# voice_sample.net
KiCad netlist of a schematic drawn in Altium Designer
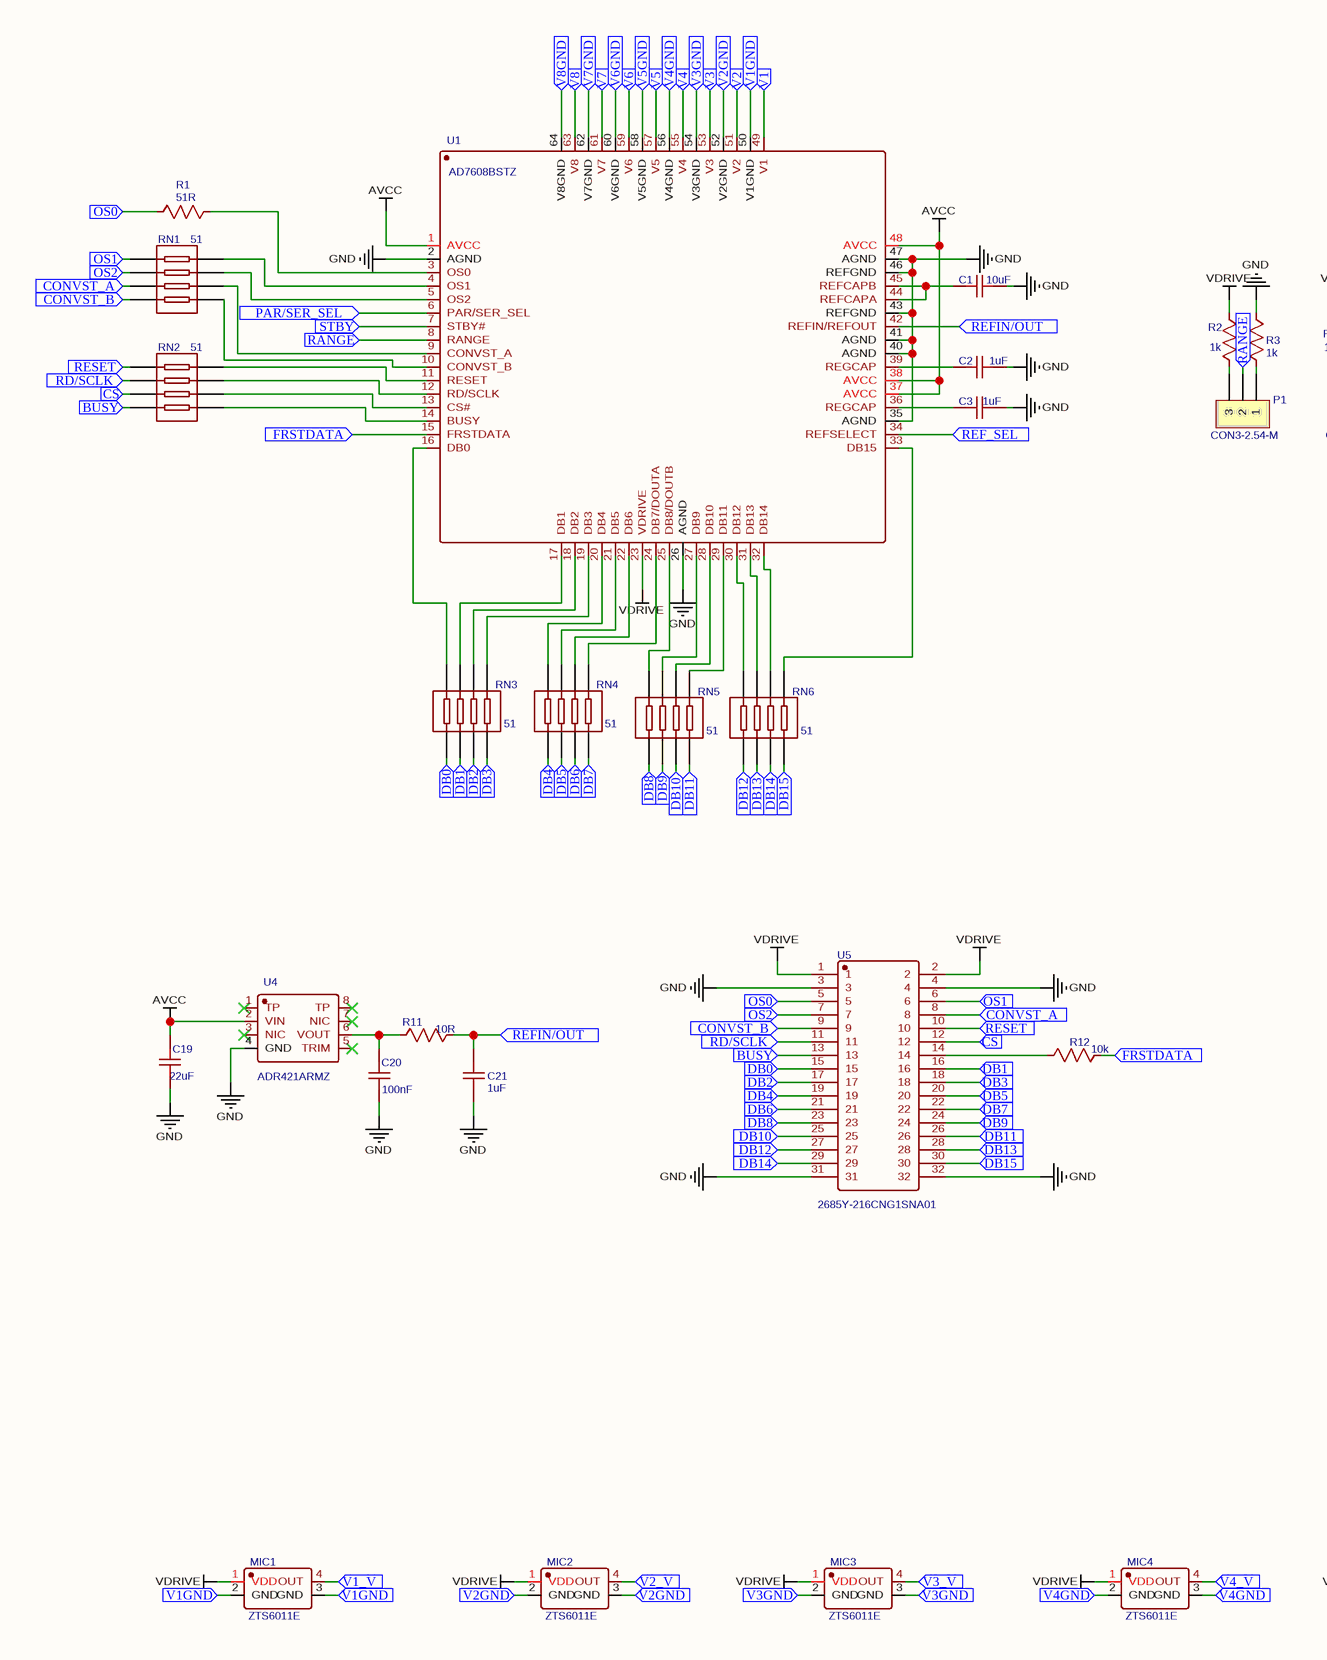
[diagram p0: voice_sample.schdoc, left]
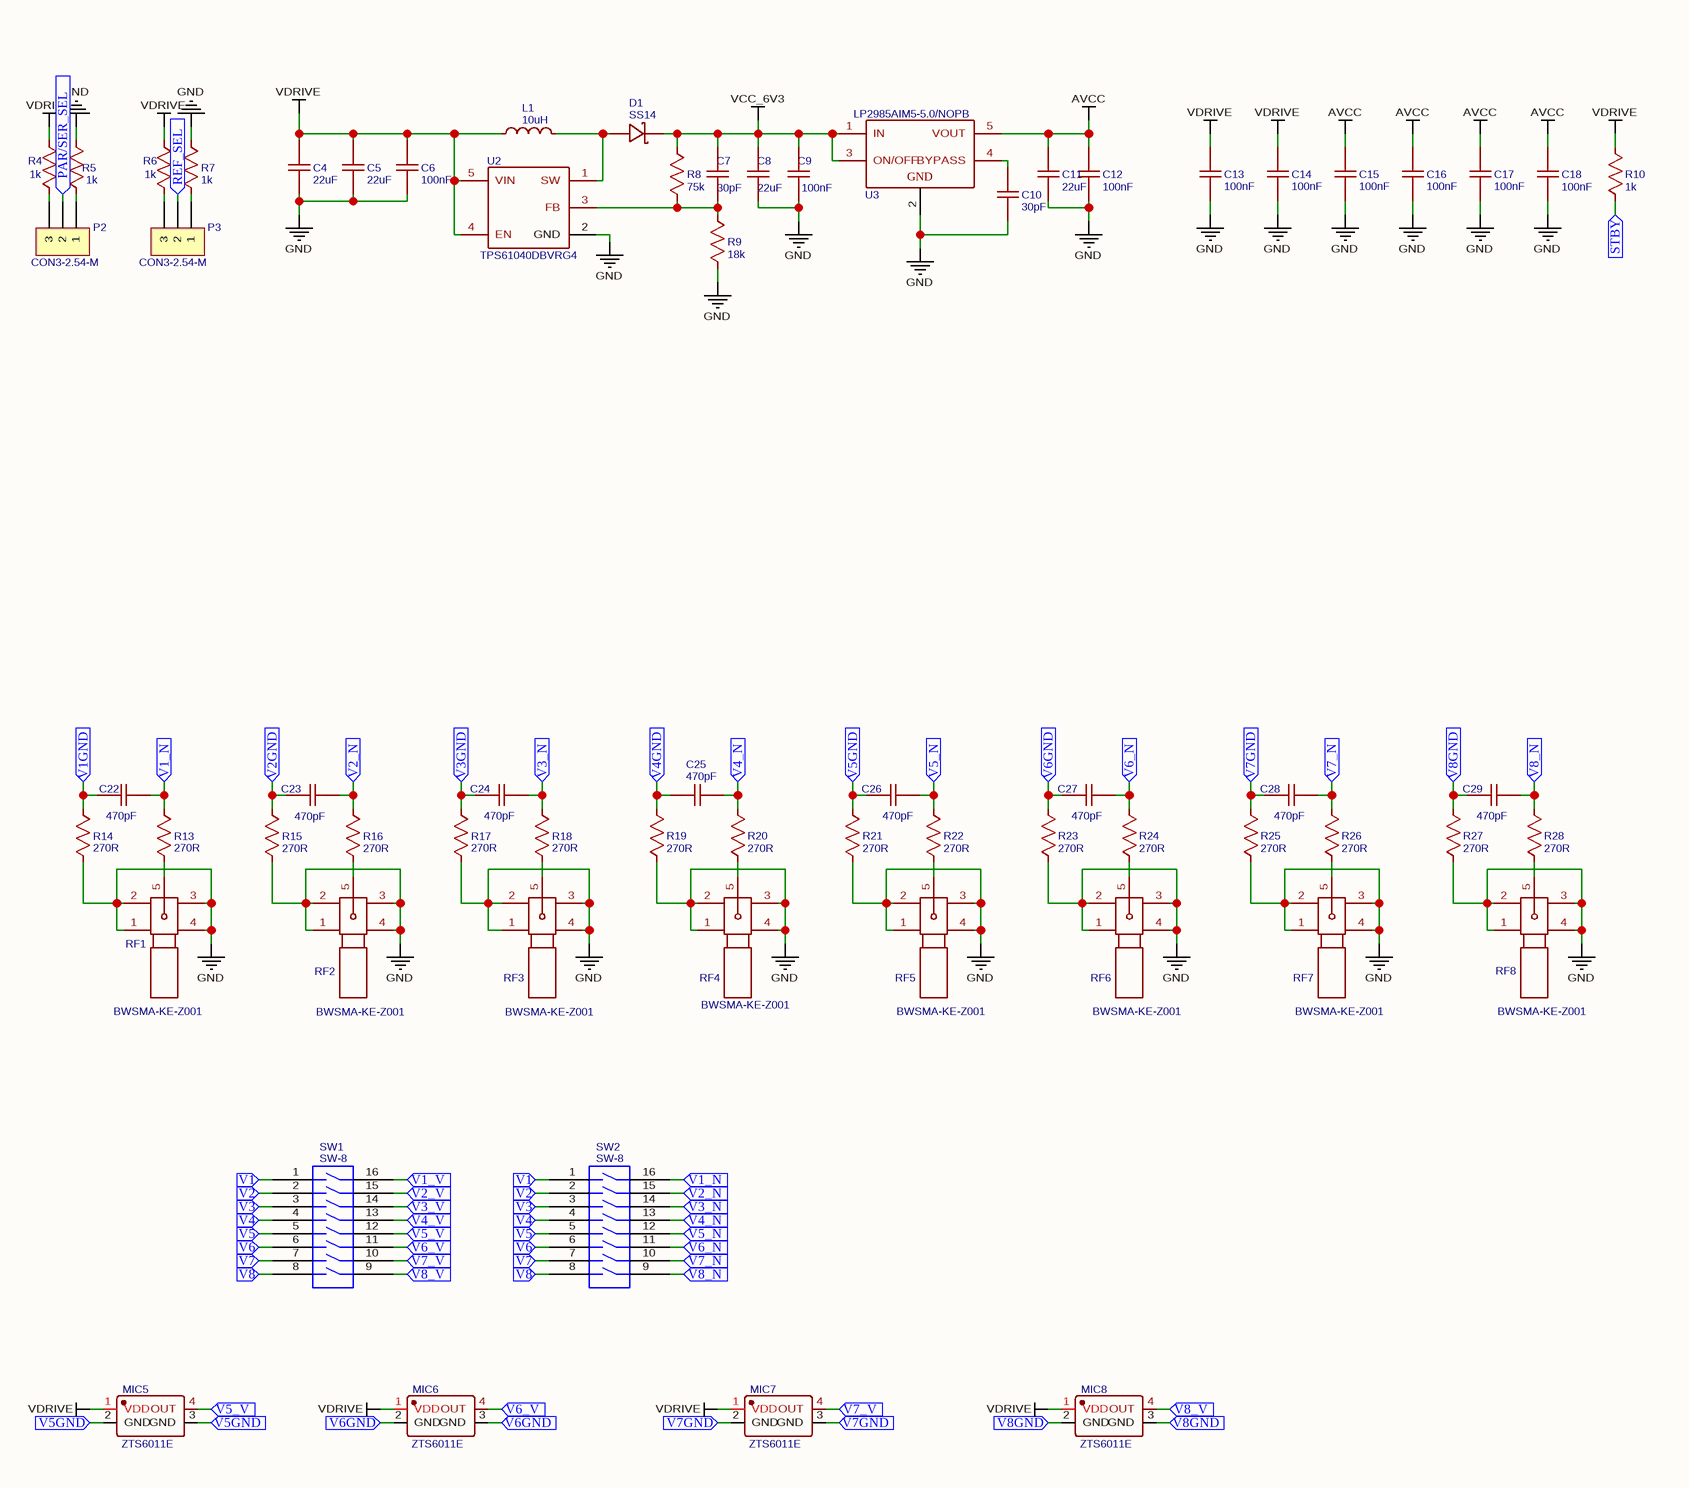
[diagram p1: voice_sample.schdoc, right]

(export (version "E")
  (design (tool "Eeschema 10.0.6"))
  (components
    (comp (ref "C1") (value "10uF") (libsource (lib "altium-import") (part "root_0_10uF_")))
    (comp (ref "C2") (value "1uF") (libsource (lib "altium-import") (part "root_0_1uF_")))
    (comp (ref "C3") (value "1uF") (libsource (lib "altium-import") (part "root_0_1uF_")))
    (comp (ref "C4") (value "22uF") (libsource (lib "altium-import") (part "root_1_22uF_")))
    (comp (ref "C5") (value "22uF") (libsource (lib "altium-import") (part "root_1_22uF_")))
    (comp (ref "C6") (value "100nF") (libsource (lib "altium-import") (part "root_1_100nF_")))
    (comp (ref "C7") (value "30pF") (libsource (lib "altium-import") (part "root_1_30pF_")))
    (comp (ref "C8") (value "22uF") (libsource (lib "altium-import") (part "root_1_22uF_")))
    (comp (ref "C9") (value "100nF") (libsource (lib "altium-import") (part "root_1_100nF_")))
    (comp (ref "C10") (value "30pF") (libsource (lib "altium-import") (part "root_1_30pF_")))
    (comp (ref "C11") (value "22uF") (libsource (lib "altium-import") (part "root_1_22uF_")))
    (comp (ref "C12") (value "100nF") (libsource (lib "altium-import") (part "root_1_100nF_")))
    (comp (ref "C13") (value "100nF") (libsource (lib "altium-import") (part "root_1_100nF_")))
    (comp (ref "C14") (value "100nF") (libsource (lib "altium-import") (part "root_1_100nF_")))
    (comp (ref "C15") (value "100nF") (libsource (lib "altium-import") (part "root_1_100nF_")))
    (comp (ref "C16") (value "100nF") (libsource (lib "altium-import") (part "root_1_100nF_")))
    (comp (ref "C17") (value "100nF") (libsource (lib "altium-import") (part "root_1_100nF_")))
    (comp (ref "C18") (value "100nF") (libsource (lib "altium-import") (part "root_1_100nF_")))
    (comp (ref "C19") (value "22uF") (libsource (lib "altium-import") (part "root_1_22uF_")))
    (comp (ref "C20") (value "100nF") (libsource (lib "altium-import") (part "root_1_100nF_")))
    (comp (ref "C21") (value "1uF") (libsource (lib "altium-import") (part "root_1_1uF_")))
    (comp (ref "C22") (value "470pF") (libsource (lib "altium-import") (part "root_0_470pF_")))
    (comp (ref "C23") (value "470pF") (libsource (lib "altium-import") (part "root_0_470pF_")))
    (comp (ref "C24") (value "470pF") (libsource (lib "altium-import") (part "root_0_470pF_")))
    (comp (ref "C25") (value "470pF") (libsource (lib "altium-import") (part "root_2_470pF_")))
    (comp (ref "C26") (value "470pF") (libsource (lib "altium-import") (part "root_0_470pF_")))
    (comp (ref "C27") (value "470pF") (libsource (lib "altium-import") (part "root_0_470pF_")))
    (comp (ref "C28") (value "470pF") (libsource (lib "altium-import") (part "root_0_470pF_")))
    (comp (ref "C29") (value "470pF") (libsource (lib "altium-import") (part "root_0_470pF_")))
    (comp (ref "D1")
      (value "SS14")
      (fields (field (name "BOM_SUPPLIER PART") "C2480"))
      (libsource (lib "altium-import") (part "root_2_SS14_"))
    )
    (comp (ref "L1") (value "10uH") (libsource (lib "altium-import") (part "root_0_10uH_")))
    (comp (ref "MIC1")
      (value "ZTS6011E")
      (fields (field (name "BOM_SUPPLIER PART") "C481291"))
      (libsource (lib "altium-import") (part "root_0_ZTS6011E_"))
    )
    (comp (ref "MIC2")
      (value "ZTS6011E")
      (fields (field (name "BOM_SUPPLIER PART") "C481291"))
      (libsource (lib "altium-import") (part "root_0_ZTS6011E_"))
    )
    (comp (ref "MIC3")
      (value "ZTS6011E")
      (fields (field (name "BOM_SUPPLIER PART") "C481291"))
      (libsource (lib "altium-import") (part "root_0_ZTS6011E_"))
    )
    (comp (ref "MIC4")
      (value "ZTS6011E")
      (fields (field (name "BOM_SUPPLIER PART") "C481291"))
      (libsource (lib "altium-import") (part "root_0_ZTS6011E_"))
    )
    (comp (ref "MIC5")
      (value "ZTS6011E")
      (fields (field (name "BOM_SUPPLIER PART") "C481291"))
      (libsource (lib "altium-import") (part "root_0_ZTS6011E_"))
    )
    (comp (ref "MIC6")
      (value "ZTS6011E")
      (fields (field (name "BOM_SUPPLIER PART") "C481291"))
      (libsource (lib "altium-import") (part "root_0_ZTS6011E_"))
    )
    (comp (ref "MIC7")
      (value "ZTS6011E")
      (fields (field (name "BOM_SUPPLIER PART") "C481291"))
      (libsource (lib "altium-import") (part "root_0_ZTS6011E_"))
    )
    (comp (ref "MIC8")
      (value "ZTS6011E")
      (fields (field (name "BOM_SUPPLIER PART") "C481291"))
      (libsource (lib "altium-import") (part "root_0_ZTS6011E_"))
    )
    (comp (ref "P1") (value "CON3-2.54-M") (libsource (lib "altium-import") (part "root_3_CON3-2.54-M_")))
    (comp (ref "P2") (value "CON3-2.54-M") (libsource (lib "altium-import") (part "root_3_CON3-2.54-M_")))
    (comp (ref "P3") (value "CON3-2.54-M") (libsource (lib "altium-import") (part "root_3_CON3-2.54-M_")))
    (comp (ref "R1") (value "51R") (libsource (lib "altium-import") (part "root_0_51R_")))
    (comp (ref "R2") (value "1k") (libsource (lib "altium-import") (part "root_1_1k_")))
    (comp (ref "R3") (value "1k") (libsource (lib "altium-import") (part "root_1_1k_")))
    (comp (ref "R4") (value "1k") (libsource (lib "altium-import") (part "root_1_1k_")))
    (comp (ref "R5") (value "1k") (libsource (lib "altium-import") (part "root_1_1k_")))
    (comp (ref "R6") (value "1k") (libsource (lib "altium-import") (part "root_1_1k_")))
    (comp (ref "R7") (value "1k") (libsource (lib "altium-import") (part "root_1_1k_")))
    (comp (ref "R8") (value "75k") (libsource (lib "altium-import") (part "root_1_75k_")))
    (comp (ref "R9") (value "18k") (libsource (lib "altium-import") (part "root_1_18k_")))
    (comp (ref "R10") (value "1k") (libsource (lib "altium-import") (part "root_1_1k_")))
    (comp (ref "R11") (value "10R") (libsource (lib "altium-import") (part "root_0_10R_")))
    (comp (ref "R12") (value "10k") (libsource (lib "altium-import") (part "root_0_10k_")))
    (comp (ref "R13") (value "270R") (libsource (lib "altium-import") (part "root_1_270R_")))
    (comp (ref "R14") (value "270R") (libsource (lib "altium-import") (part "root_1_270R_")))
    (comp (ref "R15") (value "270R") (libsource (lib "altium-import") (part "root_1_270R_")))
    (comp (ref "R16") (value "270R") (libsource (lib "altium-import") (part "root_1_270R_")))
    (comp (ref "R17") (value "270R") (libsource (lib "altium-import") (part "root_1_270R_")))
    (comp (ref "R18") (value "270R") (libsource (lib "altium-import") (part "root_1_270R_")))
    (comp (ref "R19") (value "270R") (libsource (lib "altium-import") (part "root_1_270R_")))
    (comp (ref "R20") (value "270R") (libsource (lib "altium-import") (part "root_1_270R_")))
    (comp (ref "R21") (value "270R") (libsource (lib "altium-import") (part "root_1_270R_")))
    (comp (ref "R22") (value "270R") (libsource (lib "altium-import") (part "root_1_270R_")))
    (comp (ref "R23") (value "270R") (libsource (lib "altium-import") (part "root_1_270R_")))
    (comp (ref "R24") (value "270R") (libsource (lib "altium-import") (part "root_1_270R_")))
    (comp (ref "R25") (value "270R") (libsource (lib "altium-import") (part "root_1_270R_")))
    (comp (ref "R26") (value "270R") (libsource (lib "altium-import") (part "root_1_270R_")))
    (comp (ref "R27") (value "270R") (libsource (lib "altium-import") (part "root_1_270R_")))
    (comp (ref "R28") (value "270R") (libsource (lib "altium-import") (part "root_1_270R_")))
    (comp (ref "RF1")
      (value "BWSMA-KE-Z001")
      (fields (field (name "BOM_SUPPLIER PART") "C496549"))
      (libsource (lib "altium-import") (part "root_1_BWSMA-KE-Z001_"))
    )
    (comp (ref "RF2")
      (value "BWSMA-KE-Z001")
      (fields (field (name "BOM_SUPPLIER PART") "C496549"))
      (libsource (lib "altium-import") (part "root_1_BWSMA-KE-Z001_"))
    )
    (comp (ref "RF3")
      (value "BWSMA-KE-Z001")
      (fields (field (name "BOM_SUPPLIER PART") "C496549"))
      (libsource (lib "altium-import") (part "root_1_BWSMA-KE-Z001_"))
    )
    (comp (ref "RF4")
      (value "BWSMA-KE-Z001")
      (fields (field (name "BOM_SUPPLIER PART") "C496549"))
      (libsource (lib "altium-import") (part "root_1_BWSMA-KE-Z001_"))
    )
    (comp (ref "RF5")
      (value "BWSMA-KE-Z001")
      (fields (field (name "BOM_SUPPLIER PART") "C496549"))
      (libsource (lib "altium-import") (part "root_1_BWSMA-KE-Z001_"))
    )
    (comp (ref "RF6")
      (value "BWSMA-KE-Z001")
      (fields (field (name "BOM_SUPPLIER PART") "C496549"))
      (libsource (lib "altium-import") (part "root_1_BWSMA-KE-Z001_"))
    )
    (comp (ref "RF7")
      (value "BWSMA-KE-Z001")
      (fields (field (name "BOM_SUPPLIER PART") "C496549"))
      (libsource (lib "altium-import") (part "root_1_BWSMA-KE-Z001_"))
    )
    (comp (ref "RF8")
      (value "BWSMA-KE-Z001")
      (fields (field (name "BOM_SUPPLIER PART") "C496549"))
      (libsource (lib "altium-import") (part "root_1_BWSMA-KE-Z001_"))
    )
    (comp (ref "RN1")
      (value "51")
      (fields
        (field (name "BOM_MANUFACTURER PART") "RTA02-4D510JTH")
        (field (name "BOM_SUPPLIER PART") "C102639")
      )
      (libsource (lib "altium-import") (part "root_1_51_"))
    )
    (comp (ref "RN2")
      (value "51")
      (fields
        (field (name "BOM_MANUFACTURER PART") "RTA02-4D510JTH")
        (field (name "BOM_SUPPLIER PART") "C102639")
      )
      (libsource (lib "altium-import") (part "root_1_51_"))
    )
    (comp (ref "RN3")
      (value "51")
      (fields
        (field (name "BOM_MANUFACTURER PART") "RTA02-4D510JTH")
        (field (name "BOM_SUPPLIER PART") "C102639")
      )
      (libsource (lib "altium-import") (part "root_0_51_"))
    )
    (comp (ref "RN4")
      (value "51")
      (fields
        (field (name "BOM_MANUFACTURER PART") "RTA02-4D510JTH")
        (field (name "BOM_SUPPLIER PART") "C102639")
      )
      (libsource (lib "altium-import") (part "root_0_51_"))
    )
    (comp (ref "RN5")
      (value "51")
      (fields
        (field (name "BOM_MANUFACTURER PART") "RTA02-4D510JTH")
        (field (name "BOM_SUPPLIER PART") "C102639")
      )
      (libsource (lib "altium-import") (part "root_0_51_"))
    )
    (comp (ref "RN6")
      (value "51")
      (fields
        (field (name "BOM_MANUFACTURER PART") "RTA02-4D510JTH")
        (field (name "BOM_SUPPLIER PART") "C102639")
      )
      (libsource (lib "altium-import") (part "root_0_51_"))
    )
    (comp (ref "SW1") (value "SW-8") (libsource (lib "altium-import") (part "root_0_SW-8_")))
    (comp (ref "SW2") (value "SW-8") (libsource (lib "altium-import") (part "root_0_SW-8_")))
    (comp (ref "U1")
      (value "AD7608BSTZ")
      (fields (field (name "BOM_SUPPLIER PART") "C128619"))
      (libsource (lib "altium-import") (part "root_0_AD7608BSTZ_"))
    )
    (comp (ref "U2")
      (value "TPS61040DBVRG4")
      (libsource (lib "altium-import") (part "root_0_TPS61040DBVRG4_"))
    )
    (comp (ref "U3")
      (value "LP2985AIM5-5.0/NOPB")
      (fields (field (name "BOM_SUPPLIER PART") "C130188"))
      (libsource (lib "altium-import") (part "root_0_LP2985AIM5-5.0/NOPB_"))
    )
    (comp (ref "U4")
      (value "ADR421ARMZ")
      (fields (field (name "BOM_SUPPLIER PART") "C659530"))
      (libsource (lib "altium-import") (part "root_0_ADR421ARMZ_"))
    )
    (comp (ref "U5")
      (value "2685Y-216CNG1SNA01")
      (fields (field (name "BOM_SUPPLIER PART") "C350290"))
      (libsource (lib "altium-import") (part "root_3_2685Y-216CNG1SNA01_"))
    )
  )
  (nets
    (net (code "1") (name "/BUSY") (class "Default")
      (node (ref "RN2") (pin "8") (pinfunction "8_8") (pintype "passive"))
      (node (ref "U5") (pin "13") (pinfunction "13_13") (pintype "passive"))
    )
    (net (code "2") (name "/CONVST_A") (class "Default")
      (node (ref "RN1") (pin "7") (pinfunction "7_7") (pintype "passive"))
      (node (ref "U5") (pin "8") (pinfunction "8_8") (pintype "passive"))
    )
    (net (code "3") (name "/CONVST_B") (class "Default")
      (node (ref "RN1") (pin "8") (pinfunction "8_8") (pintype "passive"))
      (node (ref "U5") (pin "9") (pinfunction "9_9") (pintype "passive"))
    )
    (net (code "4") (name "/CS") (class "Default")
      (node (ref "RN2") (pin "7") (pinfunction "7_7") (pintype "passive"))
      (node (ref "U5") (pin "12") (pinfunction "12_12") (pintype "passive"))
    )
    (net (code "5") (name "/DB0") (class "Default")
      (node (ref "RN3") (pin "1") (pinfunction "1_1") (pintype "passive"))
      (node (ref "U5") (pin "15") (pinfunction "15_15") (pintype "passive"))
    )
    (net (code "6") (name "/DB1") (class "Default")
      (node (ref "RN3") (pin "2") (pinfunction "2_2") (pintype "passive"))
      (node (ref "U5") (pin "16") (pinfunction "16_16") (pintype "passive"))
    )
    (net (code "7") (name "/DB2") (class "Default")
      (node (ref "RN3") (pin "3") (pinfunction "3_3") (pintype "passive"))
      (node (ref "U5") (pin "17") (pinfunction "17_17") (pintype "passive"))
    )
    (net (code "8") (name "/DB3") (class "Default")
      (node (ref "RN3") (pin "4") (pinfunction "4_4") (pintype "passive"))
      (node (ref "U5") (pin "18") (pinfunction "18_18") (pintype "passive"))
    )
    (net (code "9") (name "/DB4") (class "Default")
      (node (ref "RN4") (pin "1") (pinfunction "1_1") (pintype "passive"))
      (node (ref "U5") (pin "19") (pinfunction "19_19") (pintype "passive"))
    )
    (net (code "10") (name "/DB5") (class "Default")
      (node (ref "RN4") (pin "2") (pinfunction "2_2") (pintype "passive"))
      (node (ref "U5") (pin "20") (pinfunction "20_20") (pintype "passive"))
    )
    (net (code "11") (name "/DB6") (class "Default")
      (node (ref "RN4") (pin "3") (pinfunction "3_3") (pintype "passive"))
      (node (ref "U5") (pin "21") (pinfunction "21_21") (pintype "passive"))
    )
    (net (code "12") (name "/DB7") (class "Default")
      (node (ref "RN4") (pin "4") (pinfunction "4_4") (pintype "passive"))
      (node (ref "U5") (pin "22") (pinfunction "22_22") (pintype "passive"))
    )
    (net (code "13") (name "/DB8") (class "Default")
      (node (ref "RN5") (pin "1") (pinfunction "1_1") (pintype "passive"))
      (node (ref "U5") (pin "23") (pinfunction "23_23") (pintype "passive"))
    )
    (net (code "14") (name "/DB9") (class "Default")
      (node (ref "RN5") (pin "2") (pinfunction "2_2") (pintype "passive"))
      (node (ref "U5") (pin "24") (pinfunction "24_24") (pintype "passive"))
    )
    (net (code "15") (name "/DB10") (class "Default")
      (node (ref "RN5") (pin "3") (pinfunction "3_3") (pintype "passive"))
      (node (ref "U5") (pin "25") (pinfunction "25_25") (pintype "passive"))
    )
    (net (code "16") (name "/DB11") (class "Default")
      (node (ref "RN5") (pin "4") (pinfunction "4_4") (pintype "passive"))
      (node (ref "U5") (pin "26") (pinfunction "26_26") (pintype "passive"))
    )
    (net (code "17") (name "/DB12") (class "Default")
      (node (ref "RN6") (pin "1") (pinfunction "1_1") (pintype "passive"))
      (node (ref "U5") (pin "27") (pinfunction "27_27") (pintype "passive"))
    )
    (net (code "18") (name "/DB13") (class "Default")
      (node (ref "RN6") (pin "2") (pinfunction "2_2") (pintype "passive"))
      (node (ref "U5") (pin "28") (pinfunction "28_28") (pintype "passive"))
    )
    (net (code "19") (name "/DB14") (class "Default")
      (node (ref "RN6") (pin "3") (pinfunction "3_3") (pintype "passive"))
      (node (ref "U5") (pin "29") (pinfunction "29_29") (pintype "passive"))
    )
    (net (code "20") (name "/DB15") (class "Default")
      (node (ref "RN6") (pin "4") (pinfunction "4_4") (pintype "passive"))
      (node (ref "U5") (pin "30") (pinfunction "30_30") (pintype "passive"))
    )
    (net (code "21") (name "/FRSTDATA") (class "Default")
      (node (ref "R12") (pin "2") (pinfunction "2_2") (pintype "passive"))
      (node (ref "U1") (pin "15") (pinfunction "FRSTDATA_15") (pintype "passive"))
    )
    (net (code "22") (name "/OS0") (class "Default")
      (node (ref "R1") (pin "1") (pinfunction "1_1") (pintype "passive"))
      (node (ref "U5") (pin "5") (pinfunction "5_5") (pintype "passive"))
    )
    (net (code "23") (name "/OS1") (class "Default")
      (node (ref "RN1") (pin "5") (pinfunction "5_5") (pintype "passive"))
      (node (ref "U5") (pin "6") (pinfunction "6_6") (pintype "passive"))
    )
    (net (code "24") (name "/OS2") (class "Default")
      (node (ref "RN1") (pin "6") (pinfunction "6_6") (pintype "passive"))
      (node (ref "U5") (pin "7") (pinfunction "7_7") (pintype "passive"))
    )
    (net (code "25") (name "/PAR{slash}SER_SEL") (class "Default")
      (node (ref "P2") (pin "2") (pinfunction "2_2") (pintype "passive"))
      (node (ref "U1") (pin "6") (pinfunction "PAR/SER_SEL_6") (pintype "passive"))
    )
    (net (code "26") (name "/RANGE") (class "Default")
      (node (ref "P1") (pin "2") (pinfunction "2_2") (pintype "passive"))
      (node (ref "U1") (pin "8") (pinfunction "RANGE_8") (pintype "passive"))
    )
    (net (code "27") (name "/RD{slash}SCLK") (class "Default")
      (node (ref "RN2") (pin "6") (pinfunction "6_6") (pintype "passive"))
      (node (ref "U5") (pin "11") (pinfunction "11_11") (pintype "passive"))
    )
    (net (code "28") (name "/REFIN{slash}OUT") (class "Default")
      (node (ref "C21") (pin "2") (pinfunction "2_2") (pintype "passive"))
      (node (ref "R11") (pin "2") (pinfunction "2_2") (pintype "passive"))
      (node (ref "U1") (pin "42") (pinfunction "REFIN/REFOUT_42") (pintype "passive"))
    )
    (net (code "29") (name "/REF_SEL") (class "Default")
      (node (ref "P3") (pin "2") (pinfunction "2_2") (pintype "passive"))
      (node (ref "U1") (pin "34") (pinfunction "REFSELECT_34") (pintype "passive"))
    )
    (net (code "30") (name "/RESET") (class "Default")
      (node (ref "RN2") (pin "5") (pinfunction "5_5") (pintype "passive"))
      (node (ref "U5") (pin "10") (pinfunction "10_10") (pintype "passive"))
    )
    (net (code "31") (name "/STBY") (class "Default")
      (node (ref "R10") (pin "1") (pinfunction "1_1") (pintype "passive"))
      (node (ref "U1") (pin "7") (pinfunction "STBY#_7") (pintype "passive"))
    )
    (net (code "32") (name "/V1") (class "Default")
      (node (ref "SW1") (pin "1") (pintype "passive"))
      (node (ref "SW2") (pin "1") (pintype "passive"))
      (node (ref "U1") (pin "49") (pinfunction "V1_49") (pintype "passive"))
    )
    (net (code "33") (name "/V1GND") (class "Default")
      (node (ref "C22") (pin "1") (pinfunction "1_1") (pintype "passive"))
      (node (ref "MIC1") (pin "2") (pinfunction "GND_2") (pintype "passive"))
      (node (ref "MIC1") (pin "3") (pinfunction "GND_3") (pintype "passive"))
      (node (ref "R14") (pin "2") (pinfunction "2_2") (pintype "passive"))
      (node (ref "U1") (pin "50") (pinfunction "V1GND_50") (pintype "passive"))
    )
    (net (code "34") (name "/V1_N") (class "Default")
      (node (ref "C22") (pin "2") (pinfunction "2_2") (pintype "passive"))
      (node (ref "R13") (pin "2") (pinfunction "2_2") (pintype "passive"))
      (node (ref "SW2") (pin "16") (pintype "passive"))
    )
    (net (code "35") (name "/V1_V") (class "Default")
      (node (ref "MIC1") (pin "4") (pinfunction "OUT_4") (pintype "passive"))
      (node (ref "SW1") (pin "16") (pintype "passive"))
    )
    (net (code "36") (name "/V2") (class "Default")
      (node (ref "SW1") (pin "2") (pintype "passive"))
      (node (ref "SW2") (pin "2") (pintype "passive"))
      (node (ref "U1") (pin "51") (pinfunction "V2_51") (pintype "passive"))
    )
    (net (code "37") (name "/V2GND") (class "Default")
      (node (ref "C23") (pin "1") (pinfunction "1_1") (pintype "passive"))
      (node (ref "MIC2") (pin "2") (pinfunction "GND_2") (pintype "passive"))
      (node (ref "MIC2") (pin "3") (pinfunction "GND_3") (pintype "passive"))
      (node (ref "R15") (pin "2") (pinfunction "2_2") (pintype "passive"))
      (node (ref "U1") (pin "52") (pinfunction "V2GND_52") (pintype "passive"))
    )
    (net (code "38") (name "/V2_N") (class "Default")
      (node (ref "C23") (pin "2") (pinfunction "2_2") (pintype "passive"))
      (node (ref "R16") (pin "2") (pinfunction "2_2") (pintype "passive"))
      (node (ref "SW2") (pin "15") (pintype "passive"))
    )
    (net (code "39") (name "/V2_V") (class "Default")
      (node (ref "MIC2") (pin "4") (pinfunction "OUT_4") (pintype "passive"))
      (node (ref "SW1") (pin "15") (pintype "passive"))
    )
    (net (code "40") (name "/V3") (class "Default")
      (node (ref "SW1") (pin "3") (pintype "passive"))
      (node (ref "SW2") (pin "3") (pintype "passive"))
      (node (ref "U1") (pin "53") (pinfunction "V3_53") (pintype "passive"))
    )
    (net (code "41") (name "/V3GND") (class "Default")
      (node (ref "C24") (pin "1") (pinfunction "1_1") (pintype "passive"))
      (node (ref "MIC3") (pin "2") (pinfunction "GND_2") (pintype "passive"))
      (node (ref "MIC3") (pin "3") (pinfunction "GND_3") (pintype "passive"))
      (node (ref "R17") (pin "2") (pinfunction "2_2") (pintype "passive"))
      (node (ref "U1") (pin "54") (pinfunction "V3GND_54") (pintype "passive"))
    )
    (net (code "42") (name "/V3_N") (class "Default")
      (node (ref "C24") (pin "2") (pinfunction "2_2") (pintype "passive"))
      (node (ref "R18") (pin "2") (pinfunction "2_2") (pintype "passive"))
      (node (ref "SW2") (pin "14") (pintype "passive"))
    )
    (net (code "43") (name "/V3_V") (class "Default")
      (node (ref "MIC3") (pin "4") (pinfunction "OUT_4") (pintype "passive"))
      (node (ref "SW1") (pin "14") (pintype "passive"))
    )
    (net (code "44") (name "/V4") (class "Default")
      (node (ref "SW1") (pin "4") (pintype "passive"))
      (node (ref "SW2") (pin "4") (pintype "passive"))
      (node (ref "U1") (pin "55") (pinfunction "V4_55") (pintype "passive"))
    )
    (net (code "45") (name "/V4GND") (class "Default")
      (node (ref "C25") (pin "2") (pinfunction "2_2") (pintype "passive"))
      (node (ref "MIC4") (pin "2") (pinfunction "GND_2") (pintype "passive"))
      (node (ref "MIC4") (pin "3") (pinfunction "GND_3") (pintype "passive"))
      (node (ref "R19") (pin "2") (pinfunction "2_2") (pintype "passive"))
      (node (ref "U1") (pin "56") (pinfunction "V4GND_56") (pintype "passive"))
    )
    (net (code "46") (name "/V4_N") (class "Default")
      (node (ref "C25") (pin "1") (pinfunction "1_1") (pintype "passive"))
      (node (ref "R20") (pin "2") (pinfunction "2_2") (pintype "passive"))
      (node (ref "SW2") (pin "13") (pintype "passive"))
    )
    (net (code "47") (name "/V4_V") (class "Default")
      (node (ref "MIC4") (pin "4") (pinfunction "OUT_4") (pintype "passive"))
      (node (ref "SW1") (pin "13") (pintype "passive"))
    )
    (net (code "48") (name "/V5") (class "Default")
      (node (ref "SW1") (pin "5") (pintype "passive"))
      (node (ref "SW2") (pin "5") (pintype "passive"))
      (node (ref "U1") (pin "57") (pinfunction "V5_57") (pintype "passive"))
    )
    (net (code "49") (name "/V5GND") (class "Default")
      (node (ref "C26") (pin "1") (pinfunction "1_1") (pintype "passive"))
      (node (ref "MIC5") (pin "2") (pinfunction "GND_2") (pintype "passive"))
      (node (ref "MIC5") (pin "3") (pinfunction "GND_3") (pintype "passive"))
      (node (ref "R21") (pin "2") (pinfunction "2_2") (pintype "passive"))
      (node (ref "U1") (pin "58") (pinfunction "V5GND_58") (pintype "passive"))
    )
    (net (code "50") (name "/V5_N") (class "Default")
      (node (ref "C26") (pin "2") (pinfunction "2_2") (pintype "passive"))
      (node (ref "R22") (pin "2") (pinfunction "2_2") (pintype "passive"))
      (node (ref "SW2") (pin "12") (pintype "passive"))
    )
    (net (code "51") (name "/V5_V") (class "Default")
      (node (ref "MIC5") (pin "4") (pinfunction "OUT_4") (pintype "passive"))
      (node (ref "SW1") (pin "12") (pintype "passive"))
    )
    (net (code "52") (name "/V6") (class "Default")
      (node (ref "SW1") (pin "6") (pintype "passive"))
      (node (ref "SW2") (pin "6") (pintype "passive"))
      (node (ref "U1") (pin "59") (pinfunction "V6_59") (pintype "passive"))
    )
    (net (code "53") (name "/V6GND") (class "Default")
      (node (ref "C27") (pin "1") (pinfunction "1_1") (pintype "passive"))
      (node (ref "MIC6") (pin "2") (pinfunction "GND_2") (pintype "passive"))
      (node (ref "MIC6") (pin "3") (pinfunction "GND_3") (pintype "passive"))
      (node (ref "R23") (pin "2") (pinfunction "2_2") (pintype "passive"))
      (node (ref "U1") (pin "60") (pinfunction "V6GND_60") (pintype "passive"))
    )
    (net (code "54") (name "/V6_N") (class "Default")
      (node (ref "C27") (pin "2") (pinfunction "2_2") (pintype "passive"))
      (node (ref "R24") (pin "2") (pinfunction "2_2") (pintype "passive"))
      (node (ref "SW2") (pin "11") (pintype "passive"))
    )
    (net (code "55") (name "/V6_V") (class "Default")
      (node (ref "MIC6") (pin "4") (pinfunction "OUT_4") (pintype "passive"))
      (node (ref "SW1") (pin "11") (pintype "passive"))
    )
    (net (code "56") (name "/V7") (class "Default")
      (node (ref "SW1") (pin "7") (pintype "passive"))
      (node (ref "SW2") (pin "7") (pintype "passive"))
      (node (ref "U1") (pin "61") (pinfunction "V7_61") (pintype "passive"))
    )
    (net (code "57") (name "/V7GND") (class "Default")
      (node (ref "C28") (pin "1") (pinfunction "1_1") (pintype "passive"))
      (node (ref "MIC7") (pin "2") (pinfunction "GND_2") (pintype "passive"))
      (node (ref "MIC7") (pin "3") (pinfunction "GND_3") (pintype "passive"))
      (node (ref "R25") (pin "2") (pinfunction "2_2") (pintype "passive"))
      (node (ref "U1") (pin "62") (pinfunction "V7GND_62") (pintype "passive"))
    )
    (net (code "58") (name "/V7_N") (class "Default")
      (node (ref "C28") (pin "2") (pinfunction "2_2") (pintype "passive"))
      (node (ref "R26") (pin "2") (pinfunction "2_2") (pintype "passive"))
      (node (ref "SW2") (pin "10") (pintype "passive"))
    )
    (net (code "59") (name "/V7_V") (class "Default")
      (node (ref "MIC7") (pin "4") (pinfunction "OUT_4") (pintype "passive"))
      (node (ref "SW1") (pin "10") (pintype "passive"))
    )
    (net (code "60") (name "/V8") (class "Default")
      (node (ref "SW1") (pin "8") (pintype "passive"))
      (node (ref "SW2") (pin "8") (pintype "passive"))
      (node (ref "U1") (pin "63") (pinfunction "V8_63") (pintype "passive"))
    )
    (net (code "61") (name "/V8GND") (class "Default")
      (node (ref "C29") (pin "1") (pinfunction "1_1") (pintype "passive"))
      (node (ref "MIC8") (pin "2") (pinfunction "GND_2") (pintype "passive"))
      (node (ref "MIC8") (pin "3") (pinfunction "GND_3") (pintype "passive"))
      (node (ref "R27") (pin "2") (pinfunction "2_2") (pintype "passive"))
      (node (ref "U1") (pin "64") (pinfunction "V8GND_64") (pintype "passive"))
    )
    (net (code "62") (name "/V8_N") (class "Default")
      (node (ref "C29") (pin "2") (pinfunction "2_2") (pintype "passive"))
      (node (ref "R28") (pin "2") (pinfunction "2_2") (pintype "passive"))
      (node (ref "SW2") (pin "9") (pintype "passive"))
    )
    (net (code "63") (name "/V8_V") (class "Default")
      (node (ref "MIC8") (pin "4") (pinfunction "OUT_4") (pintype "passive"))
      (node (ref "SW1") (pin "9") (pintype "passive"))
    )
    (net (code "64") (name "AVCC") (class "Default")
      (node (ref "C11") (pin "2") (pinfunction "2_2") (pintype "passive"))
      (node (ref "C12") (pin "2") (pinfunction "2_2") (pintype "passive"))
      (node (ref "C15") (pin "2") (pinfunction "2_2") (pintype "passive"))
      (node (ref "C16") (pin "2") (pinfunction "2_2") (pintype "passive"))
      (node (ref "C17") (pin "2") (pinfunction "2_2") (pintype "passive"))
      (node (ref "C18") (pin "2") (pinfunction "2_2") (pintype "passive"))
      (node (ref "C19") (pin "2") (pinfunction "2_2") (pintype "passive"))
      (node (ref "U1") (pin "1") (pinfunction "AVCC_1") (pintype "passive"))
      (node (ref "U1") (pin "37") (pinfunction "AVCC_37") (pintype "passive"))
      (node (ref "U1") (pin "38") (pinfunction "AVCC_38") (pintype "passive"))
      (node (ref "U1") (pin "48") (pinfunction "AVCC_48") (pintype "passive"))
      (node (ref "U3") (pin "5") (pinfunction "VOUT_5") (pintype "passive"))
      (node (ref "U4") (pin "2") (pinfunction "VIN_2") (pintype "passive"))
    )
    (net (code "65") (name "GND") (class "Default")
      (node (ref "C1") (pin "2") (pinfunction "2_2") (pintype "passive"))
      (node (ref "C10") (pin "1") (pinfunction "1_1") (pintype "passive"))
      (node (ref "C11") (pin "1") (pinfunction "1_1") (pintype "passive"))
      (node (ref "C12") (pin "1") (pinfunction "1_1") (pintype "passive"))
      (node (ref "C13") (pin "1") (pinfunction "1_1") (pintype "passive"))
      (node (ref "C14") (pin "1") (pinfunction "1_1") (pintype "passive"))
      (node (ref "C15") (pin "1") (pinfunction "1_1") (pintype "passive"))
      (node (ref "C16") (pin "1") (pinfunction "1_1") (pintype "passive"))
      (node (ref "C17") (pin "1") (pinfunction "1_1") (pintype "passive"))
      (node (ref "C18") (pin "1") (pinfunction "1_1") (pintype "passive"))
      (node (ref "C19") (pin "1") (pinfunction "1_1") (pintype "passive"))
      (node (ref "C2") (pin "2") (pinfunction "2_2") (pintype "passive"))
      (node (ref "C20") (pin "1") (pinfunction "1_1") (pintype "passive"))
      (node (ref "C21") (pin "1") (pinfunction "1_1") (pintype "passive"))
      (node (ref "C3") (pin "2") (pinfunction "2_2") (pintype "passive"))
      (node (ref "C4") (pin "1") (pinfunction "1_1") (pintype "passive"))
      (node (ref "C5") (pin "1") (pinfunction "1_1") (pintype "passive"))
      (node (ref "C6") (pin "1") (pinfunction "1_1") (pintype "passive"))
      (node (ref "C8") (pin "1") (pinfunction "1_1") (pintype "passive"))
      (node (ref "C9") (pin "1") (pinfunction "1_1") (pintype "passive"))
      (node (ref "R14") (pin "1") (pinfunction "1_1") (pintype "passive"))
      (node (ref "R15") (pin "1") (pinfunction "1_1") (pintype "passive"))
      (node (ref "R17") (pin "1") (pinfunction "1_1") (pintype "passive"))
      (node (ref "R19") (pin "1") (pinfunction "1_1") (pintype "passive"))
      (node (ref "R21") (pin "1") (pinfunction "1_1") (pintype "passive"))
      (node (ref "R23") (pin "1") (pinfunction "1_1") (pintype "passive"))
      (node (ref "R25") (pin "1") (pinfunction "1_1") (pintype "passive"))
      (node (ref "R27") (pin "1") (pinfunction "1_1") (pintype "passive"))
      (node (ref "R3") (pin "2") (pinfunction "2_2") (pintype "passive"))
      (node (ref "R5") (pin "2") (pinfunction "2_2") (pintype "passive"))
      (node (ref "R7") (pin "2") (pinfunction "2_2") (pintype "passive"))
      (node (ref "R9") (pin "1") (pinfunction "1_1") (pintype "passive"))
      (node (ref "RF1") (pin "1") (pinfunction "1_1") (pintype "passive"))
      (node (ref "RF1") (pin "2") (pinfunction "2_2") (pintype "passive"))
      (node (ref "RF1") (pin "3") (pinfunction "3_3") (pintype "passive"))
      (node (ref "RF1") (pin "4") (pinfunction "4_4") (pintype "passive"))
      (node (ref "RF2") (pin "1") (pinfunction "1_1") (pintype "passive"))
      (node (ref "RF2") (pin "2") (pinfunction "2_2") (pintype "passive"))
      (node (ref "RF2") (pin "3") (pinfunction "3_3") (pintype "passive"))
      (node (ref "RF2") (pin "4") (pinfunction "4_4") (pintype "passive"))
      (node (ref "RF3") (pin "1") (pinfunction "1_1") (pintype "passive"))
      (node (ref "RF3") (pin "2") (pinfunction "2_2") (pintype "passive"))
      (node (ref "RF3") (pin "3") (pinfunction "3_3") (pintype "passive"))
      (node (ref "RF3") (pin "4") (pinfunction "4_4") (pintype "passive"))
      (node (ref "RF4") (pin "1") (pinfunction "1_1") (pintype "passive"))
      (node (ref "RF4") (pin "2") (pinfunction "2_2") (pintype "passive"))
      (node (ref "RF4") (pin "3") (pinfunction "3_3") (pintype "passive"))
      (node (ref "RF4") (pin "4") (pinfunction "4_4") (pintype "passive"))
      (node (ref "RF5") (pin "1") (pinfunction "1_1") (pintype "passive"))
      (node (ref "RF5") (pin "2") (pinfunction "2_2") (pintype "passive"))
      (node (ref "RF5") (pin "3") (pinfunction "3_3") (pintype "passive"))
      (node (ref "RF5") (pin "4") (pinfunction "4_4") (pintype "passive"))
      (node (ref "RF6") (pin "1") (pinfunction "1_1") (pintype "passive"))
      (node (ref "RF6") (pin "2") (pinfunction "2_2") (pintype "passive"))
      (node (ref "RF6") (pin "3") (pinfunction "3_3") (pintype "passive"))
      (node (ref "RF6") (pin "4") (pinfunction "4_4") (pintype "passive"))
      (node (ref "RF7") (pin "1") (pinfunction "1_1") (pintype "passive"))
      (node (ref "RF7") (pin "2") (pinfunction "2_2") (pintype "passive"))
      (node (ref "RF7") (pin "3") (pinfunction "3_3") (pintype "passive"))
      (node (ref "RF7") (pin "4") (pinfunction "4_4") (pintype "passive"))
      (node (ref "RF8") (pin "1") (pinfunction "1_1") (pintype "passive"))
      (node (ref "RF8") (pin "2") (pinfunction "2_2") (pintype "passive"))
      (node (ref "RF8") (pin "3") (pinfunction "3_3") (pintype "passive"))
      (node (ref "RF8") (pin "4") (pinfunction "4_4") (pintype "passive"))
      (node (ref "U1") (pin "2") (pinfunction "AGND_2") (pintype "passive"))
      (node (ref "U1") (pin "26") (pinfunction "AGND_26") (pintype "passive"))
      (node (ref "U1") (pin "35") (pinfunction "AGND_35") (pintype "passive"))
      (node (ref "U1") (pin "40") (pinfunction "AGND_40") (pintype "passive"))
      (node (ref "U1") (pin "41") (pinfunction "AGND_41") (pintype "passive"))
      (node (ref "U1") (pin "43") (pinfunction "REFGND_43") (pintype "passive"))
      (node (ref "U1") (pin "46") (pinfunction "REFGND_46") (pintype "passive"))
      (node (ref "U1") (pin "47") (pinfunction "AGND_47") (pintype "passive"))
      (node (ref "U2") (pin "2") (pinfunction "GND_2") (pintype "passive"))
      (node (ref "U3") (pin "2") (pinfunction "GND_2") (pintype "passive"))
      (node (ref "U4") (pin "4") (pinfunction "GND_4") (pintype "passive"))
      (node (ref "U5") (pin "3") (pinfunction "3_3") (pintype "passive"))
      (node (ref "U5") (pin "31") (pinfunction "31_31") (pintype "passive"))
      (node (ref "U5") (pin "32") (pinfunction "32_32") (pintype "passive"))
      (node (ref "U5") (pin "4") (pinfunction "4_4") (pintype "passive"))
    )
    (net (code "66") (name "Net-(C2-Pad1)") (class "Default")
      (node (ref "C2") (pin "1") (pinfunction "1_1") (pintype "passive"))
      (node (ref "U1") (pin "39") (pinfunction "REGCAP_39") (pintype "passive"))
    )
    (net (code "67") (name "Net-(C3-Pad1)") (class "Default")
      (node (ref "C3") (pin "1") (pinfunction "1_1") (pintype "passive"))
      (node (ref "U1") (pin "36") (pinfunction "REGCAP_36") (pintype "passive"))
    )
    (net (code "68") (name "Net-(D1-A)") (class "Default")
      (node (ref "D1") (pin "2") (pinfunction "A_2") (pintype "passive"))
      (node (ref "L1") (pin "2") (pinfunction "2_2") (pintype "passive"))
      (node (ref "U2") (pin "1") (pinfunction "SW_1") (pintype "passive"))
    )
    (net (code "69") (name "Net-(P1-Pad1)") (class "Default")
      (node (ref "P1") (pin "1") (pinfunction "1_1") (pintype "passive"))
      (node (ref "R3") (pin "1") (pinfunction "1_1") (pintype "passive"))
    )
    (net (code "70") (name "Net-(P1-Pad3)") (class "Default")
      (node (ref "P1") (pin "3") (pinfunction "3_3") (pintype "passive"))
      (node (ref "R2") (pin "1") (pinfunction "1_1") (pintype "passive"))
    )
    (net (code "71") (name "Net-(P2-Pad1)") (class "Default")
      (node (ref "P2") (pin "1") (pinfunction "1_1") (pintype "passive"))
      (node (ref "R5") (pin "1") (pinfunction "1_1") (pintype "passive"))
    )
    (net (code "72") (name "Net-(P2-Pad3)") (class "Default")
      (node (ref "P2") (pin "3") (pinfunction "3_3") (pintype "passive"))
      (node (ref "R4") (pin "1") (pinfunction "1_1") (pintype "passive"))
    )
    (net (code "73") (name "Net-(P3-Pad1)") (class "Default")
      (node (ref "P3") (pin "1") (pinfunction "1_1") (pintype "passive"))
      (node (ref "R7") (pin "1") (pinfunction "1_1") (pintype "passive"))
    )
    (net (code "74") (name "Net-(P3-Pad3)") (class "Default")
      (node (ref "P3") (pin "3") (pinfunction "3_3") (pintype "passive"))
      (node (ref "R6") (pin "1") (pinfunction "1_1") (pintype "passive"))
    )
    (net (code "75") (name "Net-(R12-Pad1)") (class "Default")
      (node (ref "R12") (pin "1") (pinfunction "1_1") (pintype "passive"))
      (node (ref "U5") (pin "14") (pinfunction "14_14") (pintype "passive"))
    )
    (net (code "76") (name "Net-(R13-Pad1)") (class "Default")
      (node (ref "R13") (pin "1") (pinfunction "1_1") (pintype "passive"))
      (node (ref "RF1") (pin "5") (pinfunction "5_5") (pintype "passive"))
    )
    (net (code "77") (name "Net-(R16-Pad1)") (class "Default")
      (node (ref "R16") (pin "1") (pinfunction "1_1") (pintype "passive"))
      (node (ref "RF2") (pin "5") (pinfunction "5_5") (pintype "passive"))
    )
    (net (code "78") (name "Net-(R18-Pad1)") (class "Default")
      (node (ref "R18") (pin "1") (pinfunction "1_1") (pintype "passive"))
      (node (ref "RF3") (pin "5") (pinfunction "5_5") (pintype "passive"))
    )
    (net (code "79") (name "Net-(R20-Pad1)") (class "Default")
      (node (ref "R20") (pin "1") (pinfunction "1_1") (pintype "passive"))
      (node (ref "RF4") (pin "5") (pinfunction "5_5") (pintype "passive"))
    )
    (net (code "80") (name "Net-(R22-Pad1)") (class "Default")
      (node (ref "R22") (pin "1") (pinfunction "1_1") (pintype "passive"))
      (node (ref "RF5") (pin "5") (pinfunction "5_5") (pintype "passive"))
    )
    (net (code "81") (name "Net-(R24-Pad1)") (class "Default")
      (node (ref "R24") (pin "1") (pinfunction "1_1") (pintype "passive"))
      (node (ref "RF6") (pin "5") (pinfunction "5_5") (pintype "passive"))
    )
    (net (code "82") (name "Net-(R26-Pad1)") (class "Default")
      (node (ref "R26") (pin "1") (pinfunction "1_1") (pintype "passive"))
      (node (ref "RF7") (pin "5") (pinfunction "5_5") (pintype "passive"))
    )
    (net (code "83") (name "Net-(R28-Pad1)") (class "Default")
      (node (ref "R28") (pin "1") (pinfunction "1_1") (pintype "passive"))
      (node (ref "RF8") (pin "5") (pinfunction "5_5") (pintype "passive"))
    )
    (net (code "84") (name "Net-(U1-BUSY)") (class "Default")
      (node (ref "RN2") (pin "1") (pinfunction "1_1") (pintype "passive"))
      (node (ref "U1") (pin "14") (pinfunction "BUSY_14") (pintype "passive"))
    )
    (net (code "85") (name "Net-(U1-CONVST_A)") (class "Default")
      (node (ref "RN1") (pin "2") (pinfunction "2_2") (pintype "passive"))
      (node (ref "U1") (pin "9") (pinfunction "CONVST_A_9") (pintype "passive"))
    )
    (net (code "86") (name "Net-(U1-CONVST_B)") (class "Default")
      (node (ref "RN1") (pin "1") (pinfunction "1_1") (pintype "passive"))
      (node (ref "U1") (pin "10") (pinfunction "CONVST_B_10") (pintype "passive"))
    )
    (net (code "87") (name "Net-(U1-CS#)") (class "Default")
      (node (ref "RN2") (pin "2") (pinfunction "2_2") (pintype "passive"))
      (node (ref "U1") (pin "13") (pinfunction "CS#_13") (pintype "passive"))
    )
    (net (code "88") (name "Net-(U1-DB0)") (class "Default")
      (node (ref "RN3") (pin "8") (pinfunction "8_8") (pintype "passive"))
      (node (ref "U1") (pin "16") (pinfunction "DB0_16") (pintype "passive"))
    )
    (net (code "89") (name "Net-(U1-DB1)") (class "Default")
      (node (ref "RN3") (pin "7") (pinfunction "7_7") (pintype "passive"))
      (node (ref "U1") (pin "17") (pinfunction "DB1_17") (pintype "passive"))
    )
    (net (code "90") (name "Net-(U1-DB2)") (class "Default")
      (node (ref "RN3") (pin "6") (pinfunction "6_6") (pintype "passive"))
      (node (ref "U1") (pin "18") (pinfunction "DB2_18") (pintype "passive"))
    )
    (net (code "91") (name "Net-(U1-DB3)") (class "Default")
      (node (ref "RN3") (pin "5") (pinfunction "5_5") (pintype "passive"))
      (node (ref "U1") (pin "19") (pinfunction "DB3_19") (pintype "passive"))
    )
    (net (code "92") (name "Net-(U1-DB4)") (class "Default")
      (node (ref "RN4") (pin "8") (pinfunction "8_8") (pintype "passive"))
      (node (ref "U1") (pin "20") (pinfunction "DB4_20") (pintype "passive"))
    )
    (net (code "93") (name "Net-(U1-DB5)") (class "Default")
      (node (ref "RN4") (pin "7") (pinfunction "7_7") (pintype "passive"))
      (node (ref "U1") (pin "21") (pinfunction "DB5_21") (pintype "passive"))
    )
    (net (code "94") (name "Net-(U1-DB6)") (class "Default")
      (node (ref "RN4") (pin "6") (pinfunction "6_6") (pintype "passive"))
      (node (ref "U1") (pin "22") (pinfunction "DB6_22") (pintype "passive"))
    )
    (net (code "95") (name "Net-(U1-DB7{slash}DOUTA)") (class "Default")
      (node (ref "RN4") (pin "5") (pinfunction "5_5") (pintype "passive"))
      (node (ref "U1") (pin "24") (pinfunction "DB7/DOUTA_24") (pintype "passive"))
    )
    (net (code "96") (name "Net-(U1-DB8{slash}DOUTB)") (class "Default")
      (node (ref "RN5") (pin "8") (pinfunction "8_8") (pintype "passive"))
      (node (ref "U1") (pin "25") (pinfunction "DB8/DOUTB_25") (pintype "passive"))
    )
    (net (code "97") (name "Net-(U1-DB9)") (class "Default")
      (node (ref "RN5") (pin "7") (pinfunction "7_7") (pintype "passive"))
      (node (ref "U1") (pin "27") (pinfunction "DB9_27") (pintype "passive"))
    )
    (net (code "98") (name "Net-(U1-DB10)") (class "Default")
      (node (ref "RN5") (pin "6") (pinfunction "6_6") (pintype "passive"))
      (node (ref "U1") (pin "28") (pinfunction "DB10_28") (pintype "passive"))
    )
    (net (code "99") (name "Net-(U1-DB11)") (class "Default")
      (node (ref "RN5") (pin "5") (pinfunction "5_5") (pintype "passive"))
      (node (ref "U1") (pin "29") (pinfunction "DB11_29") (pintype "passive"))
    )
    (net (code "100") (name "Net-(U1-DB12)") (class "Default")
      (node (ref "RN6") (pin "8") (pinfunction "8_8") (pintype "passive"))
      (node (ref "U1") (pin "30") (pinfunction "DB12_30") (pintype "passive"))
    )
    (net (code "101") (name "Net-(U1-DB13)") (class "Default")
      (node (ref "RN6") (pin "7") (pinfunction "7_7") (pintype "passive"))
      (node (ref "U1") (pin "31") (pinfunction "DB13_31") (pintype "passive"))
    )
    (net (code "102") (name "Net-(U1-DB14)") (class "Default")
      (node (ref "RN6") (pin "6") (pinfunction "6_6") (pintype "passive"))
      (node (ref "U1") (pin "32") (pinfunction "DB14_32") (pintype "passive"))
    )
    (net (code "103") (name "Net-(U1-DB15)") (class "Default")
      (node (ref "RN6") (pin "5") (pinfunction "5_5") (pintype "passive"))
      (node (ref "U1") (pin "33") (pinfunction "DB15_33") (pintype "passive"))
    )
    (net (code "104") (name "Net-(U1-OS0)") (class "Default")
      (node (ref "R1") (pin "2") (pinfunction "2_2") (pintype "passive"))
      (node (ref "U1") (pin "3") (pinfunction "OS0_3") (pintype "passive"))
    )
    (net (code "105") (name "Net-(U1-OS1)") (class "Default")
      (node (ref "RN1") (pin "4") (pinfunction "4_4") (pintype "passive"))
      (node (ref "U1") (pin "4") (pinfunction "OS1_4") (pintype "passive"))
    )
    (net (code "106") (name "Net-(U1-OS2)") (class "Default")
      (node (ref "RN1") (pin "3") (pinfunction "3_3") (pintype "passive"))
      (node (ref "U1") (pin "5") (pinfunction "OS2_5") (pintype "passive"))
    )
    (net (code "107") (name "Net-(U1-RD{slash}SCLK)") (class "Default")
      (node (ref "RN2") (pin "3") (pinfunction "3_3") (pintype "passive"))
      (node (ref "U1") (pin "12") (pinfunction "RD/SCLK_12") (pintype "passive"))
    )
    (net (code "108") (name "Net-(U1-REFCAPA)") (class "Default")
      (node (ref "C1") (pin "1") (pinfunction "1_1") (pintype "passive"))
      (node (ref "U1") (pin "44") (pinfunction "REFCAPA_44") (pintype "passive"))
      (node (ref "U1") (pin "45") (pinfunction "REFCAPB_45") (pintype "passive"))
    )
    (net (code "109") (name "Net-(U1-RESET)") (class "Default")
      (node (ref "RN2") (pin "4") (pinfunction "4_4") (pintype "passive"))
      (node (ref "U1") (pin "11") (pinfunction "RESET_11") (pintype "passive"))
    )
    (net (code "110") (name "Net-(U2-FB)") (class "Default")
      (node (ref "C7") (pin "1") (pinfunction "1_1") (pintype "passive"))
      (node (ref "R8") (pin "1") (pinfunction "1_1") (pintype "passive"))
      (node (ref "R9") (pin "2") (pinfunction "2_2") (pintype "passive"))
      (node (ref "U2") (pin "3") (pinfunction "FB_3") (pintype "passive"))
    )
    (net (code "111") (name "Net-(U3-BYPASS)") (class "Default")
      (node (ref "C10") (pin "2") (pinfunction "2_2") (pintype "passive"))
      (node (ref "U3") (pin "4") (pinfunction "BYPASS_4") (pintype "passive"))
    )
    (net (code "112") (name "Net-(U4-VOUT)") (class "Default")
      (node (ref "C20") (pin "2") (pinfunction "2_2") (pintype "passive"))
      (node (ref "R11") (pin "1") (pinfunction "1_1") (pintype "passive"))
      (node (ref "U4") (pin "6") (pinfunction "VOUT_6") (pintype "passive"))
    )
    (net (code "113") (name "VCC_6V3") (class "Default")
      (node (ref "C7") (pin "2") (pinfunction "2_2") (pintype "passive"))
      (node (ref "C8") (pin "2") (pinfunction "2_2") (pintype "passive"))
      (node (ref "C9") (pin "2") (pinfunction "2_2") (pintype "passive"))
      (node (ref "D1") (pin "1") (pinfunction "K_1") (pintype "passive"))
      (node (ref "R8") (pin "2") (pinfunction "2_2") (pintype "passive"))
      (node (ref "U3") (pin "1") (pinfunction "IN_1") (pintype "passive"))
      (node (ref "U3") (pin "3") (pinfunction "ON/OFF_3") (pintype "passive"))
    )
    (net (code "114") (name "VDRIVE") (class "Default")
      (node (ref "C13") (pin "2") (pinfunction "2_2") (pintype "passive"))
      (node (ref "C14") (pin "2") (pinfunction "2_2") (pintype "passive"))
      (node (ref "C4") (pin "2") (pinfunction "2_2") (pintype "passive"))
      (node (ref "C5") (pin "2") (pinfunction "2_2") (pintype "passive"))
      (node (ref "C6") (pin "2") (pinfunction "2_2") (pintype "passive"))
      (node (ref "L1") (pin "1") (pinfunction "1_1") (pintype "passive"))
      (node (ref "MIC1") (pin "1") (pinfunction "VDD_1") (pintype "passive"))
      (node (ref "MIC2") (pin "1") (pinfunction "VDD_1") (pintype "passive"))
      (node (ref "MIC3") (pin "1") (pinfunction "VDD_1") (pintype "passive"))
      (node (ref "MIC4") (pin "1") (pinfunction "VDD_1") (pintype "passive"))
      (node (ref "MIC5") (pin "1") (pinfunction "VDD_1") (pintype "passive"))
      (node (ref "MIC6") (pin "1") (pinfunction "VDD_1") (pintype "passive"))
      (node (ref "MIC7") (pin "1") (pinfunction "VDD_1") (pintype "passive"))
      (node (ref "MIC8") (pin "1") (pinfunction "VDD_1") (pintype "passive"))
      (node (ref "R10") (pin "2") (pinfunction "2_2") (pintype "passive"))
      (node (ref "R2") (pin "2") (pinfunction "2_2") (pintype "passive"))
      (node (ref "R4") (pin "2") (pinfunction "2_2") (pintype "passive"))
      (node (ref "R6") (pin "2") (pinfunction "2_2") (pintype "passive"))
      (node (ref "U1") (pin "23") (pinfunction "VDRIVE_23") (pintype "passive"))
      (node (ref "U2") (pin "4") (pinfunction "EN_4") (pintype "passive"))
      (node (ref "U2") (pin "5") (pinfunction "VIN_5") (pintype "passive"))
      (node (ref "U5") (pin "1") (pinfunction "1_1") (pintype "passive"))
      (node (ref "U5") (pin "2") (pinfunction "2_2") (pintype "passive"))
    )
    (net (code "115") (name "unconnected-(U4-NIC-Pad3)") (class "Default")
      (node (ref "U4") (pin "3") (pinfunction "NIC_3") (pintype "passive+no_connect"))
    )
    (net (code "116") (name "unconnected-(U4-NIC-Pad7)") (class "Default")
      (node (ref "U4") (pin "7") (pinfunction "NIC_7") (pintype "passive+no_connect"))
    )
    (net (code "117") (name "unconnected-(U4-TP-Pad1)") (class "Default")
      (node (ref "U4") (pin "1") (pinfunction "TP_1") (pintype "passive+no_connect"))
    )
    (net (code "118") (name "unconnected-(U4-TP-Pad8)") (class "Default")
      (node (ref "U4") (pin "8") (pinfunction "TP_8") (pintype "passive+no_connect"))
    )
    (net (code "119") (name "unconnected-(U4-TRIM-Pad5)") (class "Default")
      (node (ref "U4") (pin "5") (pinfunction "TRIM_5") (pintype "passive+no_connect"))
    )
  )
)
